# XIAO_Board.net
KiCad netlist of a schematic drawn in EasyEDA Pro
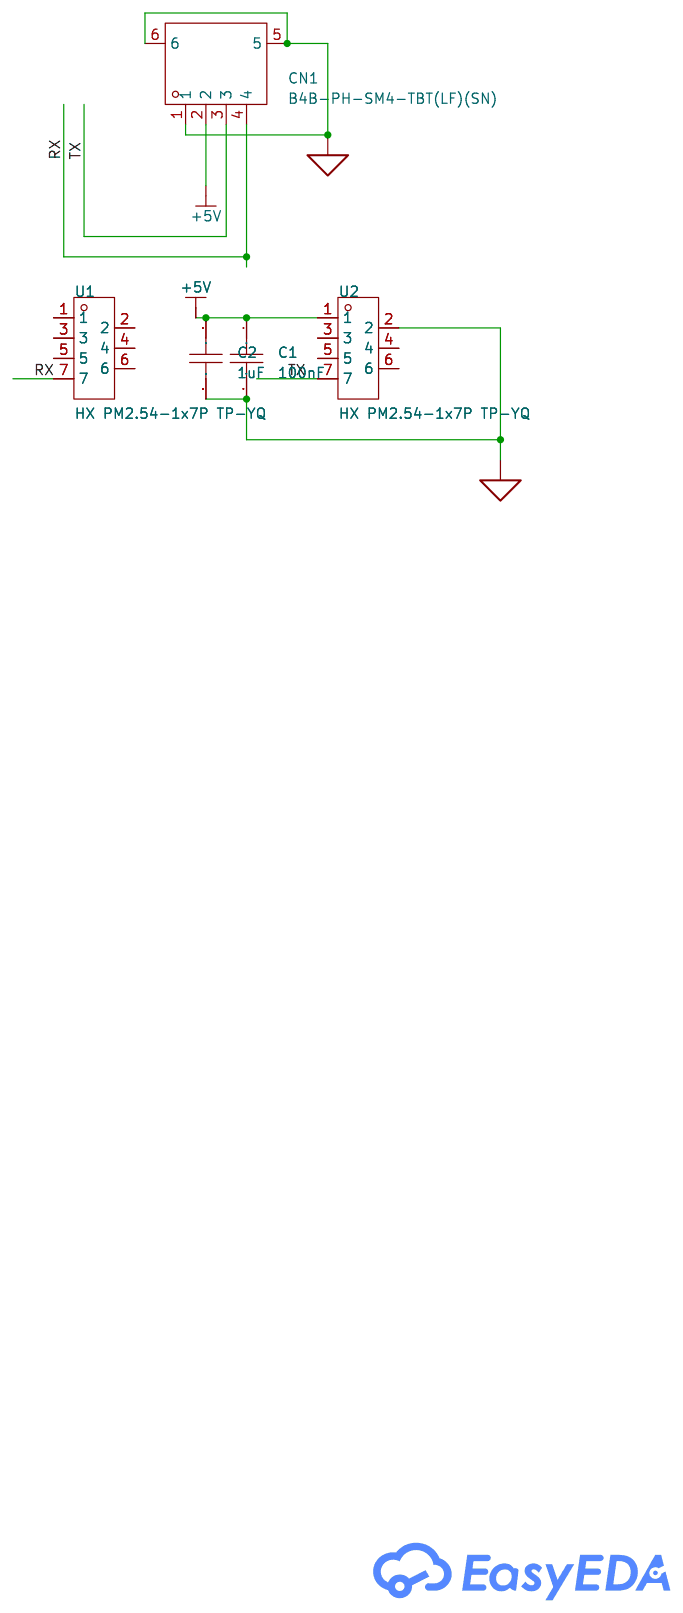
[diagram p0: schematic sheet]

(export (version "E")
  (design (tool "Eeschema 10.0.6"))
  (components
    (comp (ref "C1")
      (value "100nF")
      (footprint "easyedapro:C0603")
      (description "Capacitance:100nF Tolerance:±10% Tolerance:±10% Voltage Rating:50V Temperature Coefficient:X7R")
      (fields
        (field (name "Manufacturer Part") "CL10B104KB8NNNC")
        (field (name "Manufacturer") "SAMSUNG(三星)")
      )
      (libsource (lib "easyedapro") (part "CAP"))
    )
    (comp (ref "C2")
      (value "1uF")
      (footprint "easyedapro:C0603")
      (description "Capacitance:1uF Tolerance:±10% Tolerance:±10% Voltage Rating:50V Temperature Coefficient:X5R")
      (fields
        (field (name "Manufacturer Part") "CGA0603X5R105K500JT")
        (field (name "Manufacturer") "HRE(芯声)")
      )
      (libsource (lib "easyedapro") (part "CAP"))
    )
    (comp (ref "CN1")
      (value "B4B-PH-SM4-TBT(LF)(SN)")
      (footprint "easyedapro:CONN-SMD_B4B-PH-SM4-TBT-LF-SN")
      (fields (field (name "Manufacturer") "JST"))
      (libsource (lib "easyedapro") (part "B4B-PH-SM4-TBT(LF)(SN)"))
    )
    (comp (ref "U1")
      (value "HX PM2.54-1x7P TP-YQ")
      (footprint "easyedapro:HDR-SMD_7P-P2.54_HX-PM2.54-1X7P-TP-YQ")
      (fields (field (name "Manufacturer") "hanxia(韩下)"))
      (libsource (lib "easyedapro") (part "HX PM2.54-1X7P TP-YQ"))
    )
    (comp (ref "U2")
      (value "HX PM2.54-1x7P TP-YQ")
      (footprint "easyedapro:HDR-SMD_7P-P2.54_HX-PM2.54-1X7P-TP-YQ")
      (fields (field (name "Manufacturer") "hanxia(韩下)"))
      (libsource (lib "easyedapro") (part "HX PM2.54-1X7P TP-YQ"))
    )
  )
  (nets
    (net (code "1") (name "+5V") (class "Default")
      (node (ref "C1") (pin "1") (pinfunction "1_1") (pintype "input"))
      (node (ref "C2") (pin "1") (pinfunction "1_1") (pintype "input"))
      (node (ref "CN1") (pin "2") (pinfunction "2_2") (pintype "unspecified"))
      (node (ref "U2") (pin "1") (pinfunction "1_1") (pintype "unspecified"))
    )
    (net (code "2") (name "/RX") (class "Default")
      (node (ref "CN1") (pin "4") (pinfunction "4_4") (pintype "unspecified"))
      (node (ref "U1") (pin "7") (pinfunction "7_7") (pintype "unspecified"))
    )
    (net (code "3") (name "/TX") (class "Default")
      (node (ref "CN1") (pin "3") (pinfunction "3_3") (pintype "unspecified"))
      (node (ref "U2") (pin "7") (pinfunction "7_7") (pintype "unspecified"))
    )
    (net (code "4") (name "GND") (class "Default")
      (node (ref "C1") (pin "2") (pinfunction "2_2") (pintype "input"))
      (node (ref "C2") (pin "2") (pinfunction "2_2") (pintype "input"))
      (node (ref "CN1") (pin "1") (pinfunction "1_1") (pintype "unspecified"))
      (node (ref "CN1") (pin "5") (pinfunction "5_5") (pintype "unspecified"))
      (node (ref "CN1") (pin "6") (pinfunction "6_6") (pintype "unspecified"))
      (node (ref "U2") (pin "2") (pinfunction "2_2") (pintype "unspecified"))
    )
    (net (code "5") (name "unconnected-(U1-Pad1)") (class "Default")
      (node (ref "U1") (pin "1") (pinfunction "1_1") (pintype "unspecified"))
    )
    (net (code "6") (name "unconnected-(U1-Pad2)") (class "Default")
      (node (ref "U1") (pin "2") (pinfunction "2_2") (pintype "unspecified"))
    )
    (net (code "7") (name "unconnected-(U1-Pad3)") (class "Default")
      (node (ref "U1") (pin "3") (pinfunction "3_3") (pintype "unspecified"))
    )
    (net (code "8") (name "unconnected-(U1-Pad4)") (class "Default")
      (node (ref "U1") (pin "4") (pinfunction "4_4") (pintype "unspecified"))
    )
    (net (code "9") (name "unconnected-(U1-Pad5)") (class "Default")
      (node (ref "U1") (pin "5") (pinfunction "5_5") (pintype "unspecified"))
    )
    (net (code "10") (name "unconnected-(U1-Pad6)") (class "Default")
      (node (ref "U1") (pin "6") (pinfunction "6_6") (pintype "unspecified"))
    )
    (net (code "11") (name "unconnected-(U2-Pad3)") (class "Default")
      (node (ref "U2") (pin "3") (pinfunction "3_3") (pintype "unspecified"))
    )
    (net (code "12") (name "unconnected-(U2-Pad4)") (class "Default")
      (node (ref "U2") (pin "4") (pinfunction "4_4") (pintype "unspecified"))
    )
    (net (code "13") (name "unconnected-(U2-Pad5)") (class "Default")
      (node (ref "U2") (pin "5") (pinfunction "5_5") (pintype "unspecified"))
    )
    (net (code "14") (name "unconnected-(U2-Pad6)") (class "Default")
      (node (ref "U2") (pin "6") (pinfunction "6_6") (pintype "unspecified"))
    )
  )
)
